# PCB.net
KiCad netlist of a schematic drawn in EasyEDA Pro
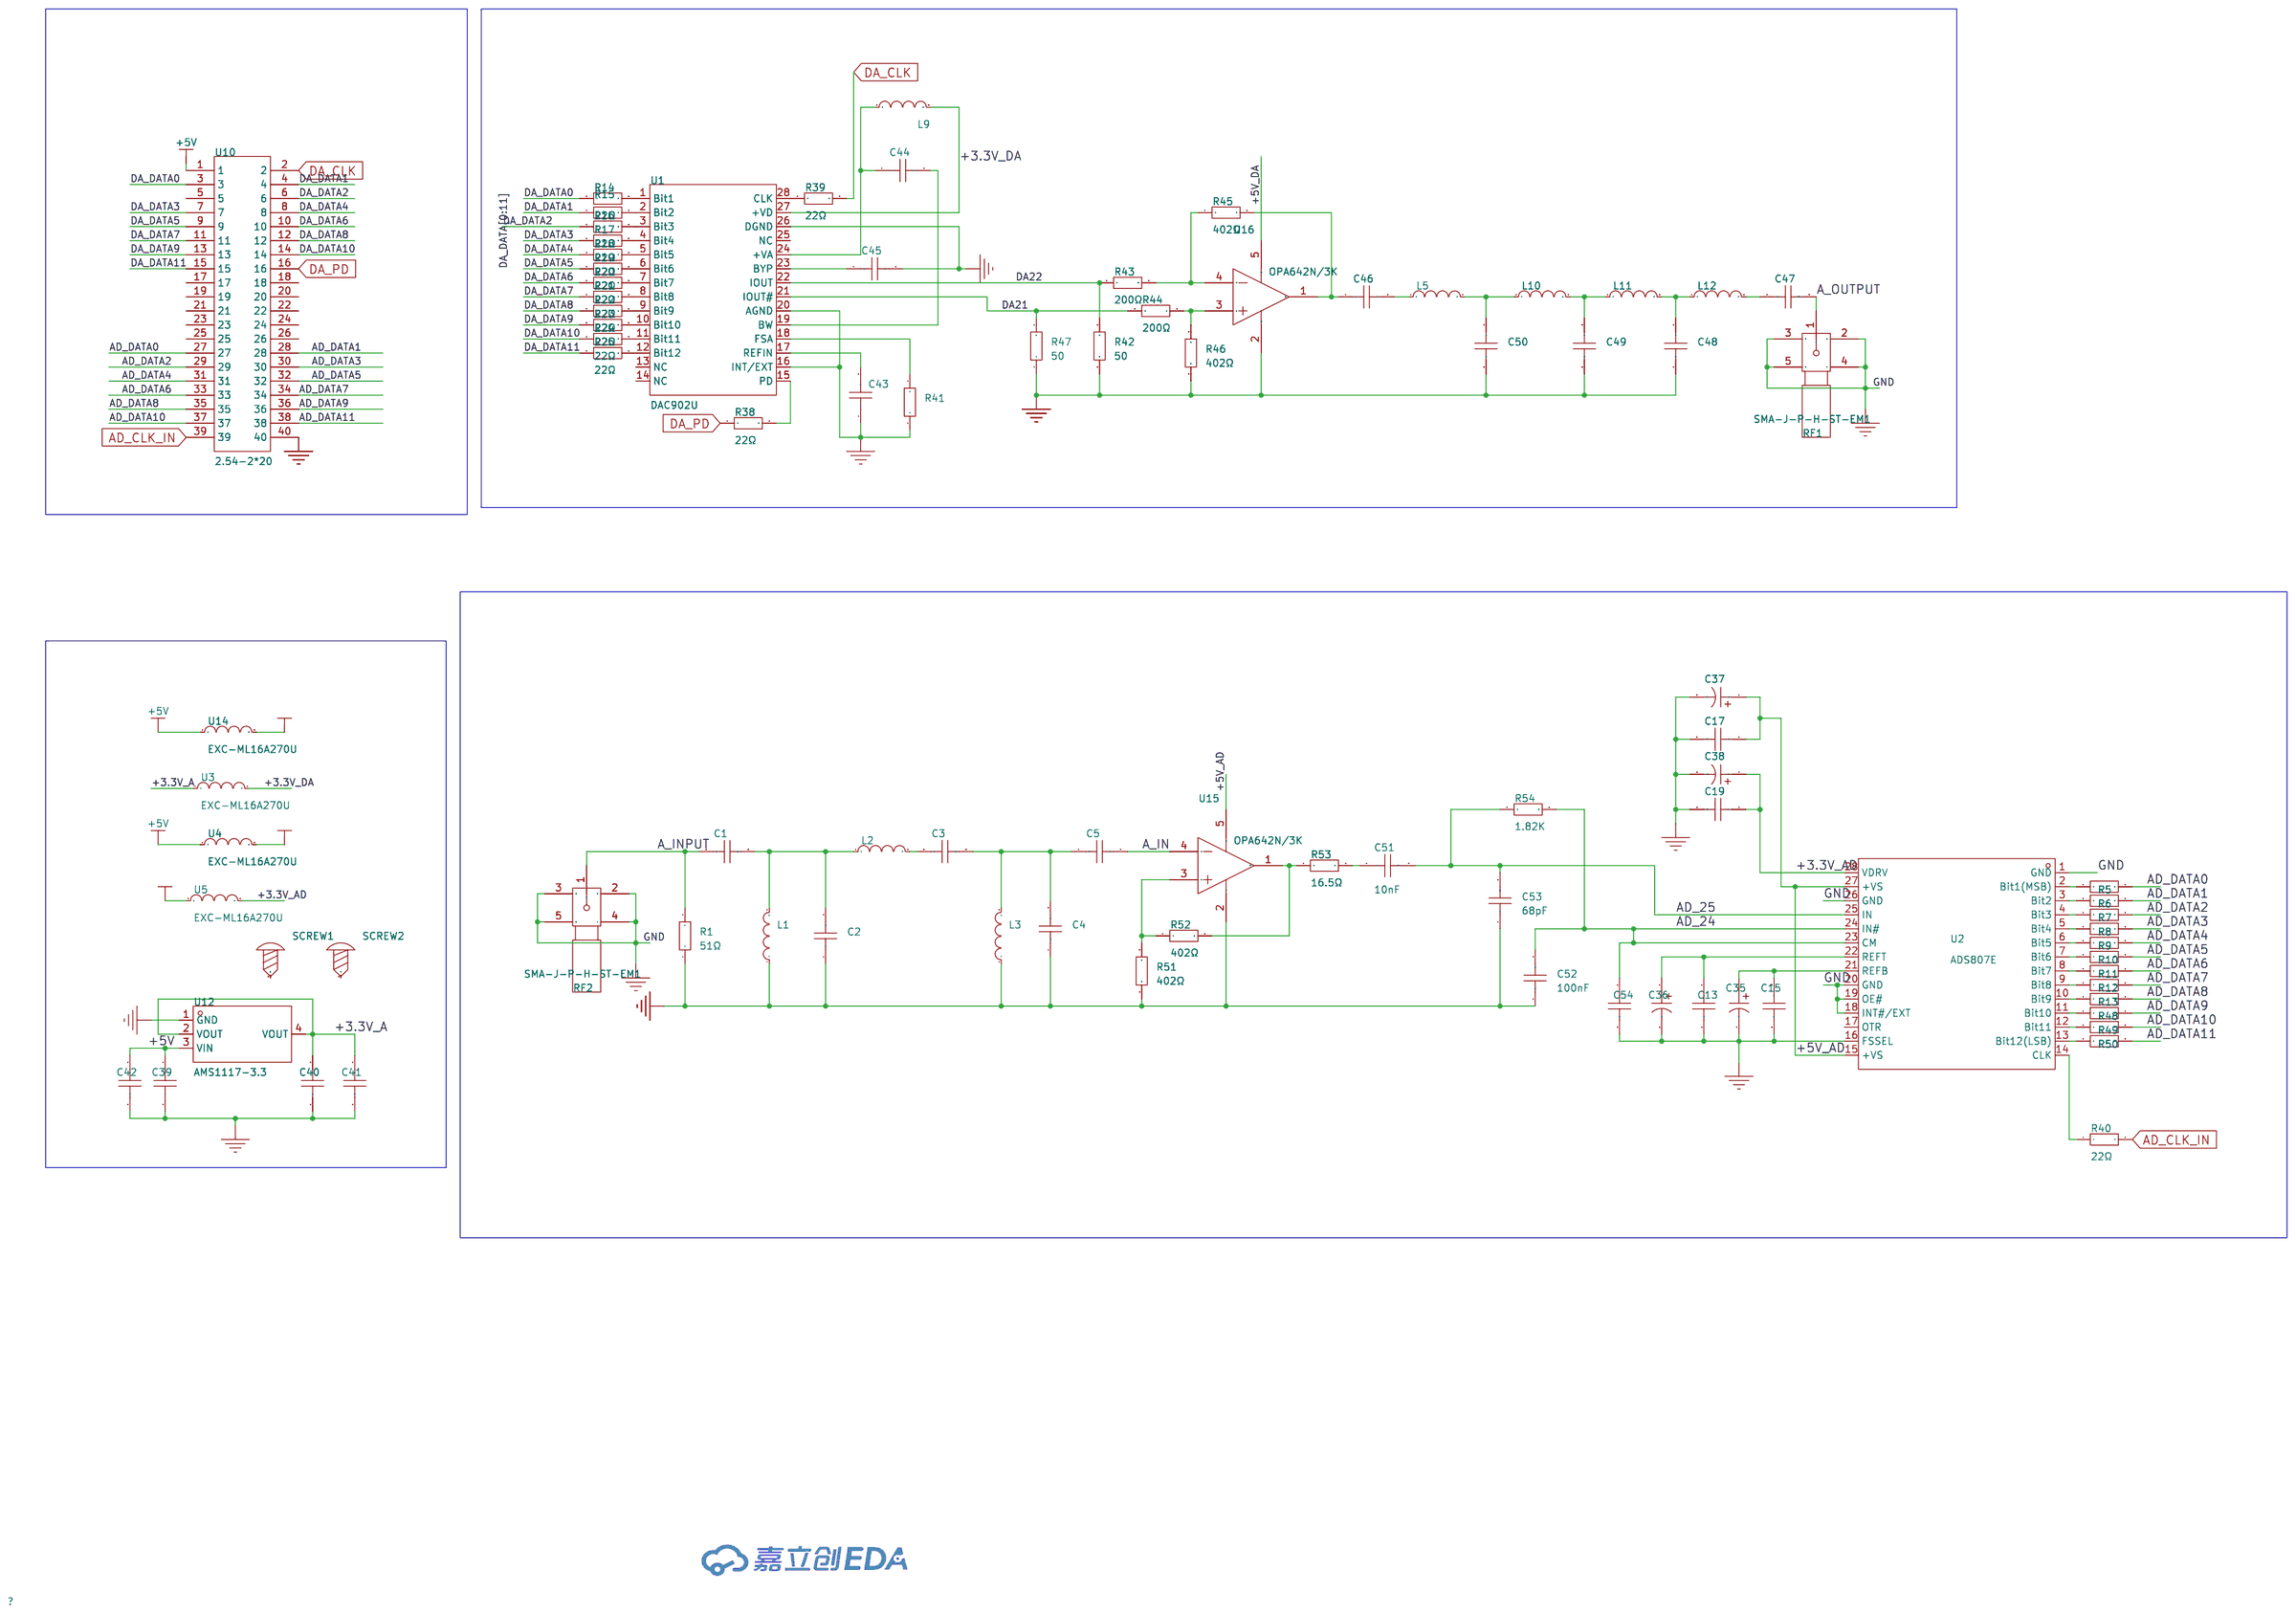
[diagram p0: schematic sheet]

(export (version "E")
  (design (tool "Eeschema 10.0.6"))
  (components
    (comp (ref "C1")
      (value "100nF")
      (footprint "easyedapro:D0805")
      (fields
        (field (name "Manufacturer Part") "CC0805KRX7R9BB104")
        (field (name "Manufacturer") "YAGEO(国巨)")
      )
      (libsource (lib "easyedapro") (part "CAP_0603"))
    )
    (comp (ref "C2")
      (value "100nF")
      (footprint "easyedapro:D0805")
      (fields
        (field (name "Manufacturer Part") "CC0805KRX7R9BB104")
        (field (name "Manufacturer") "YAGEO(国巨)")
      )
      (libsource (lib "easyedapro") (part "CAP_0603"))
    )
    (comp (ref "C3")
      (value "100nF")
      (footprint "easyedapro:D0805")
      (fields
        (field (name "Manufacturer Part") "CC0805KRX7R9BB104")
        (field (name "Manufacturer") "YAGEO(国巨)")
      )
      (libsource (lib "easyedapro") (part "CAP_0603"))
    )
    (comp (ref "C4")
      (value "100nF")
      (footprint "easyedapro:D0805")
      (fields
        (field (name "Manufacturer Part") "CC0805KRX7R9BB104")
        (field (name "Manufacturer") "YAGEO(国巨)")
      )
      (libsource (lib "easyedapro") (part "CAP_0603"))
    )
    (comp (ref "C5")
      (value "100nF")
      (footprint "easyedapro:D0805")
      (fields
        (field (name "Manufacturer Part") "CC0805KRX7R9BB104")
        (field (name "Manufacturer") "YAGEO(国巨)")
      )
      (libsource (lib "easyedapro") (part "CAP_0603"))
    )
    (comp (ref "C13")
      (value "100nF")
      (footprint "easyedapro:D0805")
      (fields
        (field (name "Manufacturer Part") "CC0805KRX7R9BB104")
        (field (name "Manufacturer") "YAGEO(国巨)")
      )
      (libsource (lib "easyedapro") (part "CAP_0603"))
    )
    (comp (ref "C15")
      (value "100nF")
      (footprint "easyedapro:D0805")
      (fields
        (field (name "Manufacturer Part") "CC0805KRX7R9BB104")
        (field (name "Manufacturer") "YAGEO(国巨)")
      )
      (libsource (lib "easyedapro") (part "CAP_0603"))
    )
    (comp (ref "C17")
      (value "100nF")
      (footprint "easyedapro:D0805")
      (fields
        (field (name "Manufacturer Part") "CC0805KRX7R9BB104")
        (field (name "Manufacturer") "YAGEO(国巨)")
      )
      (libsource (lib "easyedapro") (part "CAP_0603"))
    )
    (comp (ref "C19")
      (value "100nF")
      (footprint "easyedapro:D0805")
      (fields
        (field (name "Manufacturer Part") "CC0805KRX7R9BB104")
        (field (name "Manufacturer") "YAGEO(国巨)")
      )
      (libsource (lib "easyedapro") (part "CAP_0603"))
    )
    (comp (ref "C35")
      (value "10uF")
      (footprint "easyedapro:R1206-1")
      (fields
        (field (name "Manufacturer Part") "GVT1E227M0608CNVC")
        (field (name "Manufacturer") "HRK(鸿瑞凯电子)")
      )
      (libsource (lib "easyedapro") (part "GVT1E227M0608CNVC"))
    )
    (comp (ref "C36")
      (value "10uF")
      (footprint "easyedapro:R1206-1")
      (fields
        (field (name "Manufacturer Part") "GVT1E227M0608CNVC")
        (field (name "Manufacturer") "HRK(鸿瑞凯电子)")
      )
      (libsource (lib "easyedapro") (part "GVT1E227M0608CNVC"))
    )
    (comp (ref "C37")
      (value "10uF")
      (footprint "easyedapro:R1206-1")
      (fields
        (field (name "Manufacturer Part") "GVT1E227M0608CNVC")
        (field (name "Manufacturer") "HRK(鸿瑞凯电子)")
      )
      (libsource (lib "easyedapro") (part "GVT1E227M0608CNVC"))
    )
    (comp (ref "C38")
      (value "10uF")
      (footprint "easyedapro:R1206-1")
      (fields
        (field (name "Manufacturer Part") "GVT1E227M0608CNVC")
        (field (name "Manufacturer") "HRK(鸿瑞凯电子)")
      )
      (libsource (lib "easyedapro") (part "GVT1E227M0608CNVC"))
    )
    (comp (ref "C39")
      (value "100nF")
      (footprint "easyedapro:D0805")
      (fields (field (name "Manufacturer Part") "0805B104K500NT") (field (name "Manufacturer") "FH(风华)"))
      (libsource (lib "easyedapro") (part "CAP_0603"))
    )
    (comp (ref "C40")
      (value "100nF")
      (footprint "easyedapro:D0805")
      (fields (field (name "Manufacturer Part") "0805B104K500NT") (field (name "Manufacturer") "FH(风华)"))
      (libsource (lib "easyedapro") (part "CAP_0603"))
    )
    (comp (ref "C41")
      (value "22uF")
      (footprint "easyedapro:D0805")
      (fields
        (field (name "Manufacturer Part") "CL21A226MAQNNNE")
        (field (name "Manufacturer") "SAMSUNG(三星)")
      )
      (libsource (lib "easyedapro") (part "CAP_0603"))
    )
    (comp (ref "C42")
      (value "22uF")
      (footprint "easyedapro:D0805")
      (fields
        (field (name "Manufacturer Part") "CL21A226MAQNNNE")
        (field (name "Manufacturer") "SAMSUNG(三星)")
      )
      (libsource (lib "easyedapro") (part "CAP_0603"))
    )
    (comp (ref "C43")
      (value "100nF")
      (footprint "easyedapro:D0805")
      (fields
        (field (name "Manufacturer Part") "CC0805KRX7R9BB104")
        (field (name "Manufacturer") "YAGEO(国巨)")
      )
      (libsource (lib "easyedapro") (part "CAP_0603"))
    )
    (comp (ref "C44")
      (value "100nF")
      (footprint "easyedapro:D0805")
      (fields
        (field (name "Manufacturer Part") "CC0805KRX7R9BB104")
        (field (name "Manufacturer") "YAGEO(国巨)")
      )
      (libsource (lib "easyedapro") (part "CAP_0603"))
    )
    (comp (ref "C45")
      (value "100nF")
      (footprint "easyedapro:D0805")
      (fields
        (field (name "Manufacturer Part") "CC0805KRX7R9BB104")
        (field (name "Manufacturer") "YAGEO(国巨)")
      )
      (libsource (lib "easyedapro") (part "CAP_0603"))
    )
    (comp (ref "C46")
      (value "100nF")
      (footprint "easyedapro:D0805")
      (fields
        (field (name "Manufacturer Part") "CC0805KRX7R9BB104")
        (field (name "Manufacturer") "YAGEO(国巨)")
      )
      (libsource (lib "easyedapro") (part "CAP_0603"))
    )
    (comp (ref "C47")
      (value "100nF")
      (footprint "easyedapro:D0805")
      (fields
        (field (name "Manufacturer Part") "CC0805KRX7R9BB104")
        (field (name "Manufacturer") "YAGEO(国巨)")
      )
      (libsource (lib "easyedapro") (part "CAP_0603"))
    )
    (comp (ref "C48")
      (value "500pF")
      (footprint "easyedapro:D0805")
      (fields (field (name "Manufacturer Part") "0805CG501J500NT") (field (name "Manufacturer") "FH(风华)"))
      (libsource (lib "easyedapro") (part "CAP_0603"))
    )
    (comp (ref "C49")
      (value "850pF")
      (footprint "easyedapro:D0805")
      (fields
        (field (name "Manufacturer Part") "C06BL851X-5ZN-X0T")
        (field (name "Manufacturer") "Knowles(楼氏)")
      )
      (libsource (lib "easyedapro") (part "CAP_0603"))
    )
    (comp (ref "C50")
      (value "500pF")
      (footprint "easyedapro:D0805")
      (fields (field (name "Manufacturer Part") "0805CG501J500NT") (field (name "Manufacturer") "FH(风华)"))
      (libsource (lib "easyedapro") (part "CAP_0603"))
    )
    (comp (ref "C51")
      (value "10nF")
      (footprint "easyedapro:C0603")
      (fields
        (field (name "Manufacturer Part") "CC0805KRX7R9BB104")
        (field (name "Manufacturer") "YAGEO(国巨)")
      )
      (libsource (lib "easyedapro") (part "Capacitance"))
    )
    (comp (ref "C52")
      (value "100nF")
      (footprint "easyedapro:C0603")
      (fields
        (field (name "Manufacturer Part") "CC0805KRX7R9BB104")
        (field (name "Manufacturer") "YAGEO(国巨)")
      )
      (libsource (lib "easyedapro") (part "Capacitance"))
    )
    (comp (ref "C53")
      (value "68pF")
      (footprint "easyedapro:C0603")
      (fields (field (name "Manufacturer Part") "0805CG680J500NT") (field (name "Manufacturer") "FH(风华)"))
      (libsource (lib "easyedapro") (part "Capacitance"))
    )
    (comp (ref "C54")
      (value "100nF")
      (footprint "easyedapro:D0805")
      (fields
        (field (name "Manufacturer Part") "CC0805KRX7R9BB104")
        (field (name "Manufacturer") "YAGEO(国巨)")
      )
      (libsource (lib "easyedapro") (part "CAP_0603"))
    )
    (comp (ref "L1")
      (value "1uH")
      (footprint "easyedapro:D0805")
      (fields
        (field (name "Manufacturer Part") "SDFL2012Q1R0KTF")
        (field (name "Manufacturer") "Sunlord(顺络)")
      )
      (libsource (lib "easyedapro") (part "L_0603"))
    )
    (comp (ref "L2")
      (value "1uH")
      (footprint "easyedapro:D0805")
      (fields
        (field (name "Manufacturer Part") "SDFL2012Q1R0KTF")
        (field (name "Manufacturer") "Sunlord(顺络)")
      )
      (libsource (lib "easyedapro") (part "L_0603"))
    )
    (comp (ref "L3")
      (value "1uH")
      (footprint "easyedapro:D0805")
      (fields
        (field (name "Manufacturer Part") "SDFL2012Q1R0KTF")
        (field (name "Manufacturer") "Sunlord(顺络)")
      )
      (libsource (lib "easyedapro") (part "L_0603"))
    )
    (comp (ref "L5")
      (value "500nH")
      (footprint "easyedapro:D0805")
      (fields
        (field (name "Manufacturer Part") "CKP1608DR50M-T")
        (field (name "Manufacturer") "TAIYO YUDEN(太诱)")
      )
      (libsource (lib "easyedapro") (part "L_0603"))
    )
    (comp (ref "L9")
      (value "1uH")
      (footprint "easyedapro:D0805")
      (fields
        (field (name "Manufacturer Part") "SDFL2012Q1R0KTF")
        (field (name "Manufacturer") "Sunlord(顺络)")
      )
      (libsource (lib "easyedapro") (part "L_0603"))
    )
    (comp (ref "L10")
      (value "2uH")
      (footprint "easyedapro:D0805")
      (fields (field (name "Manufacturer Part") "LQW21FT2R0M0HL") (field (name "Manufacturer") "muRata(村田)"))
      (libsource (lib "easyedapro") (part "L_0603"))
    )
    (comp (ref "L11")
      (value "2uH")
      (footprint "easyedapro:D0805")
      (fields (field (name "Manufacturer Part") "LQW21FT2R0M0HL") (field (name "Manufacturer") "muRata(村田)"))
      (libsource (lib "easyedapro") (part "L_0603"))
    )
    (comp (ref "L12")
      (value "500nH")
      (footprint "easyedapro:D0805")
      (fields
        (field (name "Manufacturer Part") "CKP1608DR50M-T")
        (field (name "Manufacturer") "TAIYO YUDEN(太诱)")
      )
      (libsource (lib "easyedapro") (part "L_0603"))
    )
    (comp (ref "R1")
      (value "51Ω")
      (footprint "easyedapro:R0603")
      (fields
        (field (name "Manufacturer Part") "0805W8F510JT5E")
        (field (name "Manufacturer") "UNI-ROYAL(厚声)")
      )
      (libsource (lib "easyedapro") (part "电阻"))
    )
    (comp (ref "R5")
      (value "22Ω")
      (footprint "easyedapro:R0805")
      (fields
        (field (name "Manufacturer Part") "0805W8F2002T5E")
        (field (name "Manufacturer") "UNI-ROYAL(厚声)")
      )
      (libsource (lib "easyedapro") (part "0805W8F2002T5E"))
    )
    (comp (ref "R6")
      (value "22Ω")
      (footprint "easyedapro:R0805")
      (fields
        (field (name "Manufacturer Part") "0805W8F2002T5E")
        (field (name "Manufacturer") "UNI-ROYAL(厚声)")
      )
      (libsource (lib "easyedapro") (part "0805W8F2002T5E"))
    )
    (comp (ref "R7")
      (value "22Ω")
      (footprint "easyedapro:R0805")
      (fields
        (field (name "Manufacturer Part") "0805W8F2002T5E")
        (field (name "Manufacturer") "UNI-ROYAL(厚声)")
      )
      (libsource (lib "easyedapro") (part "0805W8F2002T5E"))
    )
    (comp (ref "R8")
      (value "22Ω")
      (footprint "easyedapro:R0805")
      (fields
        (field (name "Manufacturer Part") "0805W8F2002T5E")
        (field (name "Manufacturer") "UNI-ROYAL(厚声)")
      )
      (libsource (lib "easyedapro") (part "0805W8F2002T5E"))
    )
    (comp (ref "R9")
      (value "22Ω")
      (footprint "easyedapro:R0805")
      (fields
        (field (name "Manufacturer Part") "0805W8F2002T5E")
        (field (name "Manufacturer") "UNI-ROYAL(厚声)")
      )
      (libsource (lib "easyedapro") (part "0805W8F2002T5E"))
    )
    (comp (ref "R10")
      (value "22Ω")
      (footprint "easyedapro:R0805")
      (fields
        (field (name "Manufacturer Part") "0805W8F2002T5E")
        (field (name "Manufacturer") "UNI-ROYAL(厚声)")
      )
      (libsource (lib "easyedapro") (part "0805W8F2002T5E"))
    )
    (comp (ref "R11")
      (value "22Ω")
      (footprint "easyedapro:R0805")
      (fields
        (field (name "Manufacturer Part") "0805W8F2002T5E")
        (field (name "Manufacturer") "UNI-ROYAL(厚声)")
      )
      (libsource (lib "easyedapro") (part "0805W8F2002T5E"))
    )
    (comp (ref "R12")
      (value "22Ω")
      (footprint "easyedapro:R0805")
      (fields
        (field (name "Manufacturer Part") "0805W8F2002T5E")
        (field (name "Manufacturer") "UNI-ROYAL(厚声)")
      )
      (libsource (lib "easyedapro") (part "0805W8F2002T5E"))
    )
    (comp (ref "R13")
      (value "22Ω")
      (footprint "easyedapro:R0805")
      (fields
        (field (name "Manufacturer Part") "0805W8F2002T5E")
        (field (name "Manufacturer") "UNI-ROYAL(厚声)")
      )
      (libsource (lib "easyedapro") (part "0805W8F2002T5E"))
    )
    (comp (ref "R14")
      (value "22Ω")
      (footprint "easyedapro:R0603")
      (fields
        (field (name "Manufacturer Part") "0805W8F220JT5E")
        (field (name "Manufacturer") "UNI-ROYAL(厚声)")
      )
      (libsource (lib "easyedapro") (part "电阻"))
    )
    (comp (ref "R15")
      (value "22Ω")
      (footprint "easyedapro:R0603")
      (fields
        (field (name "Manufacturer Part") "0805W8F220JT5E")
        (field (name "Manufacturer") "UNI-ROYAL(厚声)")
      )
      (libsource (lib "easyedapro") (part "电阻"))
    )
    (comp (ref "R16")
      (value "22Ω")
      (footprint "easyedapro:R0603")
      (fields
        (field (name "Manufacturer Part") "0805W8F220JT5E")
        (field (name "Manufacturer") "UNI-ROYAL(厚声)")
      )
      (libsource (lib "easyedapro") (part "电阻"))
    )
    (comp (ref "R17")
      (value "22Ω")
      (footprint "easyedapro:R0603")
      (fields
        (field (name "Manufacturer Part") "0805W8F220JT5E")
        (field (name "Manufacturer") "UNI-ROYAL(厚声)")
      )
      (libsource (lib "easyedapro") (part "电阻"))
    )
    (comp (ref "R18")
      (value "22Ω")
      (footprint "easyedapro:R0603")
      (fields
        (field (name "Manufacturer Part") "0805W8F220JT5E")
        (field (name "Manufacturer") "UNI-ROYAL(厚声)")
      )
      (libsource (lib "easyedapro") (part "电阻"))
    )
    (comp (ref "R19")
      (value "22Ω")
      (footprint "easyedapro:R0603")
      (fields
        (field (name "Manufacturer Part") "0805W8F220JT5E")
        (field (name "Manufacturer") "UNI-ROYAL(厚声)")
      )
      (libsource (lib "easyedapro") (part "电阻"))
    )
    (comp (ref "R20")
      (value "22Ω")
      (footprint "easyedapro:R0603")
      (fields
        (field (name "Manufacturer Part") "0805W8F220JT5E")
        (field (name "Manufacturer") "UNI-ROYAL(厚声)")
      )
      (libsource (lib "easyedapro") (part "电阻"))
    )
    (comp (ref "R21")
      (value "22Ω")
      (footprint "easyedapro:R0603")
      (fields
        (field (name "Manufacturer Part") "0805W8F220JT5E")
        (field (name "Manufacturer") "UNI-ROYAL(厚声)")
      )
      (libsource (lib "easyedapro") (part "电阻"))
    )
    (comp (ref "R22")
      (value "22Ω")
      (footprint "easyedapro:R0603")
      (fields
        (field (name "Manufacturer Part") "0805W8F220JT5E")
        (field (name "Manufacturer") "UNI-ROYAL(厚声)")
      )
      (libsource (lib "easyedapro") (part "电阻"))
    )
    (comp (ref "R23")
      (value "22Ω")
      (footprint "easyedapro:R0603")
      (fields
        (field (name "Manufacturer Part") "0805W8F220JT5E")
        (field (name "Manufacturer") "UNI-ROYAL(厚声)")
      )
      (libsource (lib "easyedapro") (part "电阻"))
    )
    (comp (ref "R24")
      (value "22Ω")
      (footprint "easyedapro:R0603")
      (fields
        (field (name "Manufacturer Part") "0805W8F220JT5E")
        (field (name "Manufacturer") "UNI-ROYAL(厚声)")
      )
      (libsource (lib "easyedapro") (part "电阻"))
    )
    (comp (ref "R25")
      (value "22Ω")
      (footprint "easyedapro:R0603")
      (fields
        (field (name "Manufacturer Part") "0805W8F220JT5E")
        (field (name "Manufacturer") "UNI-ROYAL(厚声)")
      )
      (libsource (lib "easyedapro") (part "电阻"))
    )
    (comp (ref "R38")
      (value "22Ω")
      (footprint "easyedapro:R0603")
      (fields
        (field (name "Manufacturer Part") "0805W8F220JT5E")
        (field (name "Manufacturer") "UNI-ROYAL(厚声)")
      )
      (libsource (lib "easyedapro") (part "电阻"))
    )
    (comp (ref "R39")
      (value "22Ω")
      (footprint "easyedapro:R0603")
      (fields
        (field (name "Manufacturer Part") "0805W8F220JT5E")
        (field (name "Manufacturer") "UNI-ROYAL(厚声)")
      )
      (libsource (lib "easyedapro") (part "电阻"))
    )
    (comp (ref "R40")
      (value "22Ω")
      (footprint "easyedapro:R0603")
      (fields
        (field (name "Manufacturer Part") "0805W8F220JT5E")
        (field (name "Manufacturer") "UNI-ROYAL(厚声)")
      )
      (libsource (lib "easyedapro") (part "电阻"))
    )
    (comp (ref "R41")
      (value "2kΩ")
      (footprint "easyedapro:D0805")
      (fields
        (field (name "Manufacturer Part") "0805W8F2001T5E")
        (field (name "Manufacturer") "UNI-ROYAL(厚声)")
      )
      (libsource (lib "easyedapro") (part "Res_0603"))
    )
    (comp (ref "R42")
      (value "50")
      (footprint "easyedapro:R0603")
      (fields (field (name "Manufacturer Part") "ERJ6ENF28R7V") (field (name "Manufacturer") "PANASONIC(松下)"))
      (libsource (lib "easyedapro") (part "电阻"))
    )
    (comp (ref "R43")
      (value "200Ω")
      (footprint "easyedapro:R0603")
      (fields
        (field (name "Manufacturer Part") "0805W8F2000T5E")
        (field (name "Manufacturer") "UNI-ROYAL(厚声)")
      )
      (libsource (lib "easyedapro") (part "电阻"))
    )
    (comp (ref "R44")
      (value "200Ω")
      (footprint "easyedapro:R0603")
      (fields
        (field (name "Manufacturer Part") "0805W8F2000T5E")
        (field (name "Manufacturer") "UNI-ROYAL(厚声)")
      )
      (libsource (lib "easyedapro") (part "电阻"))
    )
    (comp (ref "R45")
      (value "402Ω")
      (footprint "easyedapro:R0603")
      (fields (field (name "Manufacturer Part") "FRC0805F4020TS") (field (name "Manufacturer") "FOJAN(富捷)"))
      (libsource (lib "easyedapro") (part "电阻"))
    )
    (comp (ref "R46")
      (value "402Ω")
      (footprint "easyedapro:R0603")
      (fields (field (name "Manufacturer Part") "FRC0805F4020TS") (field (name "Manufacturer") "FOJAN(富捷)"))
      (libsource (lib "easyedapro") (part "电阻"))
    )
    (comp (ref "R47")
      (value "50")
      (footprint "easyedapro:R0603")
      (fields (field (name "Manufacturer Part") "ERJ6ENF26R1V") (field (name "Manufacturer") "PANASONIC(松下)"))
      (libsource (lib "easyedapro") (part "电阻"))
    )
    (comp (ref "R48")
      (value "22Ω")
      (footprint "easyedapro:R0805")
      (fields
        (field (name "Manufacturer Part") "0805W8F2002T5E")
        (field (name "Manufacturer") "UNI-ROYAL(厚声)")
      )
      (libsource (lib "easyedapro") (part "0805W8F2002T5E"))
    )
    (comp (ref "R49")
      (value "22Ω")
      (footprint "easyedapro:R0805")
      (fields
        (field (name "Manufacturer Part") "0805W8F2002T5E")
        (field (name "Manufacturer") "UNI-ROYAL(厚声)")
      )
      (libsource (lib "easyedapro") (part "0805W8F2002T5E"))
    )
    (comp (ref "R50")
      (value "22Ω")
      (footprint "easyedapro:R0805")
      (fields
        (field (name "Manufacturer Part") "0805W8F2002T5E")
        (field (name "Manufacturer") "UNI-ROYAL(厚声)")
      )
      (libsource (lib "easyedapro") (part "0805W8F2002T5E"))
    )
    (comp (ref "R51")
      (value "402Ω")
      (footprint "easyedapro:R0603")
      (fields (field (name "Manufacturer Part") "FRC0805F4020TS") (field (name "Manufacturer") "FOJAN(富捷)"))
      (libsource (lib "easyedapro") (part "电阻"))
    )
    (comp (ref "R52")
      (value "402Ω")
      (footprint "easyedapro:R0603")
      (fields (field (name "Manufacturer Part") "FRC0805F4020TS") (field (name "Manufacturer") "FOJAN(富捷)"))
      (libsource (lib "easyedapro") (part "电阻"))
    )
    (comp (ref "R53")
      (value "16.5Ω")
      (footprint "easyedapro:R0603")
      (fields (field (name "Manufacturer Part") "RC0805FR-0716R5L") (field (name "Manufacturer") "YAGEO(国巨)"))
      (libsource (lib "easyedapro") (part "电阻"))
    )
    (comp (ref "R54")
      (value "1.82K")
      (footprint "easyedapro:R0603")
      (libsource (lib "easyedapro") (part "电阻"))
    )
    (comp (ref "RF1")
      (value "SMA-J-P-H-ST-EM1")
      (footprint "easyedapro:SMA-SMD_SMA-J-P-H-ST-EM1")
      (fields (field (name "Manufacturer") "SAMTEC"))
      (libsource (lib "easyedapro") (part "SMA-J-P-H-ST-EM1"))
    )
    (comp (ref "RF2")
      (value "SMA-J-P-H-ST-EM1")
      (footprint "easyedapro:SMA-SMD_SMA-J-P-H-ST-EM1")
      (fields (field (name "Manufacturer") "SAMTEC"))
      (libsource (lib "easyedapro") (part "SMA-J-P-H-ST-EM1"))
    )
    (comp (ref "SCREW1")
      (value "~")
      (footprint "easyedapro:M3螺丝")
      (libsource (lib "easyedapro") (part "螺丝孔"))
    )
    (comp (ref "SCREW2")
      (value "~")
      (footprint "easyedapro:M3螺丝")
      (libsource (lib "easyedapro") (part "螺丝孔"))
    )
    (comp (ref "U1")
      (value "DAC902U")
      (footprint "easyedapro:SOIC-28_L18.0-W7.5-P1.27-LS10.3-BL")
      (description "分辨率:12位;接口类型:-;工作电压:2.7V~5.5V;稳定时间:30ns;积分非线性:1LSB;")
      (fields (field (name "Manufacturer") "TI(德州仪器)"))
      (libsource (lib "easyedapro") (part "DAC902U"))
    )
    (comp (ref "U2")
      (value "ADS807E")
      (footprint "easyedapro:SSOP-28_L10.2-W5.3-P0.65-LS7.8-BL")
      (fields (field (name "Manufacturer") "TI(德州仪器)"))
      (libsource (lib "easyedapro") (part "ADS807E"))
    )
    (comp (ref "U3")
      (value "EXC-ML16A270U")
      (footprint "easyedapro:L0603")
      (fields (field (name "Manufacturer") "PANASONIC(松下)"))
      (libsource (lib "easyedapro") (part "EXC-ML16A270U"))
    )
    (comp (ref "U4")
      (value "EXC-ML16A270U")
      (footprint "easyedapro:L0603")
      (fields (field (name "Manufacturer") "PANASONIC(松下)"))
      (libsource (lib "easyedapro") (part "EXC-ML16A270U"))
    )
    (comp (ref "U5")
      (value "EXC-ML16A270U")
      (footprint "easyedapro:L0603")
      (fields (field (name "Manufacturer") "PANASONIC(松下)"))
      (libsource (lib "easyedapro") (part "EXC-ML16A270U"))
    )
    (comp (ref "U10")
      (value "2.54-2*20")
      (footprint "easyedapro:HDR-TH_40P-P2.54-V-F-R2-C20-S2.54")
      (fields (field (name "Manufacturer") "ZHOURI(洲日)"))
      (libsource (lib "easyedapro") (part "2.54-2*20"))
    )
    (comp (ref "U12")
      (value "AMS1117-3.3")
      (footprint "easyedapro:SOT-223-3_L6.5-W3.4-P2.30-LS7.0-BR")
      (fields (field (name "Manufacturer") "AMS"))
      (libsource (lib "easyedapro") (part "AMS1117-3.3_C6186"))
    )
    (comp (ref "U14")
      (value "EXC-ML16A270U")
      (footprint "easyedapro:L0603")
      (fields (field (name "Manufacturer") "PANASONIC(松下)"))
      (libsource (lib "easyedapro") (part "EXC-ML16A270U"))
    )
    (comp (ref "U15")
      (value "OPA642N/3K")
      (footprint "easyedapro:SOT-23-5_L2.9-W1.6-P0.95-LS2.8-BR")
      (description "放大器数:单路;增益带宽积(GBP):210MHz;输入偏置电流(Ib):25uA;压摆率(SR):380V/us;带宽(-3db):-;")
      (fields (field (name "Manufacturer") "TI(德州仪器)"))
      (libsource (lib "easyedapro") (part "OPA642N/3K"))
    )
    (comp (ref "U16")
      (value "OPA642N/3K")
      (footprint "easyedapro:SOT-23-5_L2.9-W1.6-P0.95-LS2.8-BR")
      (description "放大器数:单路;增益带宽积(GBP):210MHz;输入偏置电流(Ib):25uA;压摆率(SR):380V/us;带宽(-3db):-;")
      (fields (field (name "Manufacturer") "TI(德州仪器)"))
      (libsource (lib "easyedapro") (part "OPA642N/3K"))
    )
  )
  (nets
    (net (code "1") (name "+3.3V_A") (class "Default")
      (node (ref "C40") (pin "1") (pinfunction "1_1") (pintype "unspecified"))
      (node (ref "C41") (pin "1") (pinfunction "1_1") (pintype "unspecified"))
      (node (ref "U12") (pin "2") (pinfunction "VOUT_2") (pintype "unspecified"))
      (node (ref "U12") (pin "4") (pinfunction "VOUT_4") (pintype "unspecified"))
      (node (ref "U3") (pin "1") (pinfunction "1_1") (pintype "unspecified"))
      (node (ref "U5") (pin "1") (pinfunction "1_1") (pintype "unspecified"))
    )
    (net (code "2") (name "+5V") (class "Default")
      (node (ref "C39") (pin "1") (pinfunction "1_1") (pintype "unspecified"))
      (node (ref "C42") (pin "1") (pinfunction "1_1") (pintype "unspecified"))
      (node (ref "U10") (pin "1") (pinfunction "1_1") (pintype "unspecified"))
      (node (ref "U12") (pin "3") (pinfunction "VIN_3") (pintype "unspecified"))
      (node (ref "U14") (pin "1") (pinfunction "1_1") (pintype "unspecified"))
      (node (ref "U4") (pin "1") (pinfunction "1_1") (pintype "unspecified"))
    )
    (net (code "3") (name "+5V_AD") (class "Default")
      (node (ref "C17") (pin "1") (pinfunction "1_1") (pintype "unspecified"))
      (node (ref "C37") (pin "1") (pinfunction "1_1") (pintype "unspecified"))
      (node (ref "U15") (pin "5") (pinfunction "VS+_5") (pintype "unspecified"))
      (node (ref "U2") (pin "15") (pinfunction "+VS_15") (pintype "unspecified"))
      (node (ref "U2") (pin "27") (pinfunction "+VS_27") (pintype "unspecified"))
      (node (ref "U4") (pin "2") (pinfunction "2_2") (pintype "unspecified"))
    )
    (net (code "4") (name "+5V_DA") (class "Default")
      (node (ref "U14") (pin "2") (pinfunction "2_2") (pintype "unspecified"))
      (node (ref "U16") (pin "5") (pinfunction "VS+_5") (pintype "unspecified"))
    )
    (net (code "5") (name "/+3.3V_AD") (class "Default")
      (node (ref "C19") (pin "1") (pinfunction "1_1") (pintype "unspecified"))
      (node (ref "C38") (pin "1") (pinfunction "1_1") (pintype "unspecified"))
      (node (ref "U2") (pin "28") (pinfunction "VDRV_28") (pintype "unspecified"))
      (node (ref "U5") (pin "2") (pinfunction "2_2") (pintype "unspecified"))
    )
    (net (code "6") (name "/+3.3V_DA") (class "Default")
      (node (ref "L9") (pin "2") (pinfunction "2_2") (pintype "unspecified"))
      (node (ref "U1") (pin "27") (pinfunction "+VD_27") (pintype "unspecified"))
      (node (ref "U3") (pin "2") (pinfunction "2_2") (pintype "unspecified"))
    )
    (net (code "7") (name "/AD_24") (class "Default")
      (node (ref "C52") (pin "2") (pinfunction "2_2") (pintype "input"))
      (node (ref "C54") (pin "1") (pinfunction "1_1") (pintype "unspecified"))
      (node (ref "R54") (pin "2") (pinfunction "2_2") (pintype "input"))
      (node (ref "U2") (pin "23") (pinfunction "CM_23") (pintype "unspecified"))
      (node (ref "U2") (pin "24") (pinfunction "IN#_24") (pintype "unspecified"))
    )
    (net (code "8") (name "/AD_25") (class "Default")
      (node (ref "C51") (pin "2") (pinfunction "2_2") (pintype "input"))
      (node (ref "C53") (pin "2") (pinfunction "2_2") (pintype "input"))
      (node (ref "R54") (pin "1") (pinfunction "1_1") (pintype "input"))
      (node (ref "U2") (pin "25") (pinfunction "IN_25") (pintype "unspecified"))
    )
    (net (code "9") (name "/AD_DATA0") (class "Default")
      (node (ref "R5") (pin "2") (pinfunction "2_2") (pintype "unspecified"))
      (node (ref "U10") (pin "27") (pinfunction "27_27") (pintype "unspecified"))
    )
    (net (code "10") (name "/AD_DATA1") (class "Default")
      (node (ref "R6") (pin "2") (pinfunction "2_2") (pintype "unspecified"))
      (node (ref "U10") (pin "28") (pinfunction "28_28") (pintype "unspecified"))
    )
    (net (code "11") (name "/AD_DATA2") (class "Default")
      (node (ref "R7") (pin "2") (pinfunction "2_2") (pintype "unspecified"))
      (node (ref "U10") (pin "29") (pinfunction "29_29") (pintype "unspecified"))
    )
    (net (code "12") (name "/AD_DATA3") (class "Default")
      (node (ref "R8") (pin "2") (pinfunction "2_2") (pintype "unspecified"))
      (node (ref "U10") (pin "30") (pinfunction "30_30") (pintype "unspecified"))
    )
    (net (code "13") (name "/AD_DATA4") (class "Default")
      (node (ref "R9") (pin "2") (pinfunction "2_2") (pintype "unspecified"))
      (node (ref "U10") (pin "31") (pinfunction "31_31") (pintype "unspecified"))
    )
    (net (code "14") (name "/AD_DATA5") (class "Default")
      (node (ref "R10") (pin "2") (pinfunction "2_2") (pintype "unspecified"))
      (node (ref "U10") (pin "32") (pinfunction "32_32") (pintype "unspecified"))
    )
    (net (code "15") (name "/AD_DATA6") (class "Default")
      (node (ref "R11") (pin "2") (pinfunction "2_2") (pintype "unspecified"))
      (node (ref "U10") (pin "33") (pinfunction "33_33") (pintype "unspecified"))
    )
    (net (code "16") (name "/AD_DATA7") (class "Default")
      (node (ref "R12") (pin "2") (pinfunction "2_2") (pintype "unspecified"))
      (node (ref "U10") (pin "34") (pinfunction "34_34") (pintype "unspecified"))
    )
    (net (code "17") (name "/AD_DATA8") (class "Default")
      (node (ref "R13") (pin "2") (pinfunction "2_2") (pintype "unspecified"))
      (node (ref "U10") (pin "35") (pinfunction "35_35") (pintype "unspecified"))
    )
    (net (code "18") (name "/AD_DATA9") (class "Default")
      (node (ref "R48") (pin "2") (pinfunction "2_2") (pintype "unspecified"))
      (node (ref "U10") (pin "36") (pinfunction "36_36") (pintype "unspecified"))
    )
    (net (code "19") (name "/AD_DATA10") (class "Default")
      (node (ref "R49") (pin "2") (pinfunction "2_2") (pintype "unspecified"))
      (node (ref "U10") (pin "37") (pinfunction "37_37") (pintype "unspecified"))
    )
    (net (code "20") (name "/AD_DATA11") (class "Default")
      (node (ref "R50") (pin "2") (pinfunction "2_2") (pintype "unspecified"))
      (node (ref "U10") (pin "38") (pinfunction "38_38") (pintype "unspecified"))
    )
    (net (code "21") (name "/A_IN") (class "Default")
      (node (ref "C5") (pin "2") (pinfunction "2_2") (pintype "unspecified"))
      (node (ref "U15") (pin "4") (pinfunction "-IN_4") (pintype "unspecified"))
    )
    (net (code "22") (name "/A_INPUT") (class "Default")
      (node (ref "C1") (pin "1") (pinfunction "1_1") (pintype "unspecified"))
      (node (ref "R1") (pin "2") (pinfunction "2_2") (pintype "input"))
      (node (ref "RF2") (pin "1") (pinfunction "1_1") (pintype "unspecified"))
    )
    (net (code "23") (name "/A_OUTPUT") (class "Default")
      (node (ref "C47") (pin "2") (pinfunction "2_2") (pintype "unspecified"))
      (node (ref "RF1") (pin "1") (pinfunction "1_1") (pintype "unspecified"))
    )
    (net (code "24") (name "/DA21") (class "Default")
      (node (ref "R44") (pin "1") (pinfunction "1_1") (pintype "input"))
      (node (ref "R47") (pin "2") (pinfunction "2_2") (pintype "input"))
      (node (ref "U1") (pin "21") (pinfunction "IOUT#_21") (pintype "unspecified"))
    )
    (net (code "25") (name "/DA22") (class "Default")
      (node (ref "R42") (pin "2") (pinfunction "2_2") (pintype "input"))
      (node (ref "R43") (pin "1") (pinfunction "1_1") (pintype "input"))
      (node (ref "U1") (pin "22") (pinfunction "IOUT_22") (pintype "unspecified"))
    )
    (net (code "26") (name "/DA_DATA0") (class "Default")
      (node (ref "R14") (pin "1") (pinfunction "1_1") (pintype "input"))
      (node (ref "U10") (pin "3") (pinfunction "3_3") (pintype "unspecified"))
    )
    (net (code "27") (name "/DA_DATA1") (class "Default")
      (node (ref "R15") (pin "1") (pinfunction "1_1") (pintype "input"))
      (node (ref "U10") (pin "4") (pinfunction "4_4") (pintype "unspecified"))
    )
    (net (code "28") (name "/DA_DATA2") (class "Default")
      (node (ref "R16") (pin "1") (pinfunction "1_1") (pintype "input"))
      (node (ref "U10") (pin "6") (pinfunction "6_6") (pintype "unspecified"))
    )
    (net (code "29") (name "/DA_DATA3") (class "Default")
      (node (ref "R17") (pin "1") (pinfunction "1_1") (pintype "input"))
      (node (ref "U10") (pin "7") (pinfunction "7_7") (pintype "unspecified"))
    )
    (net (code "30") (name "/DA_DATA4") (class "Default")
      (node (ref "R18") (pin "1") (pinfunction "1_1") (pintype "input"))
      (node (ref "U10") (pin "8") (pinfunction "8_8") (pintype "unspecified"))
    )
    (net (code "31") (name "/DA_DATA5") (class "Default")
      (node (ref "R19") (pin "1") (pinfunction "1_1") (pintype "input"))
      (node (ref "U10") (pin "9") (pinfunction "9_9") (pintype "unspecified"))
    )
    (net (code "32") (name "/DA_DATA6") (class "Default")
      (node (ref "R20") (pin "1") (pinfunction "1_1") (pintype "input"))
      (node (ref "U10") (pin "10") (pinfunction "10_10") (pintype "unspecified"))
    )
    (net (code "33") (name "/DA_DATA7") (class "Default")
      (node (ref "R21") (pin "1") (pinfunction "1_1") (pintype "input"))
      (node (ref "U10") (pin "11") (pinfunction "11_11") (pintype "unspecified"))
    )
    (net (code "34") (name "/DA_DATA8") (class "Default")
      (node (ref "R22") (pin "1") (pinfunction "1_1") (pintype "input"))
      (node (ref "U10") (pin "12") (pinfunction "12_12") (pintype "unspecified"))
    )
    (net (code "35") (name "/DA_DATA9") (class "Default")
      (node (ref "R23") (pin "1") (pinfunction "1_1") (pintype "input"))
      (node (ref "U10") (pin "13") (pinfunction "13_13") (pintype "unspecified"))
    )
    (net (code "36") (name "/DA_DATA10") (class "Default")
      (node (ref "R24") (pin "1") (pinfunction "1_1") (pintype "input"))
      (node (ref "U10") (pin "14") (pinfunction "14_14") (pintype "unspecified"))
    )
    (net (code "37") (name "/DA_DATA11") (class "Default")
      (node (ref "R25") (pin "1") (pinfunction "1_1") (pintype "input"))
      (node (ref "U10") (pin "15") (pinfunction "15_15") (pintype "unspecified"))
    )
    (net (code "39") (name "AD_CLK_IN") (class "Default")
      (node (ref "R40") (pin "2") (pinfunction "2_2") (pintype "input"))
      (node (ref "U10") (pin "39") (pinfunction "39_39") (pintype "unspecified"))
    )
    (net (code "40") (name "DA_CLK") (class "Default")
      (node (ref "R39") (pin "2") (pinfunction "2_2") (pintype "input"))
      (node (ref "U10") (pin "2") (pinfunction "2_2") (pintype "unspecified"))
    )
    (net (code "41") (name "DA_PD") (class "Default")
      (node (ref "R38") (pin "1") (pinfunction "1_1") (pintype "input"))
      (node (ref "U10") (pin "16") (pinfunction "16_16") (pintype "unspecified"))
    )
    (net (code "42") (name "GND") (class "Default")
      (node (ref "C13") (pin "2") (pinfunction "2_2") (pintype "unspecified"))
      (node (ref "C15") (pin "2") (pinfunction "2_2") (pintype "unspecified"))
      (node (ref "C17") (pin "2") (pinfunction "2_2") (pintype "unspecified"))
      (node (ref "C19") (pin "2") (pinfunction "2_2") (pintype "unspecified"))
      (node (ref "C2") (pin "1") (pinfunction "1_1") (pintype "unspecified"))
      (node (ref "C35") (pin "2") (pinfunction "2_2") (pintype "unspecified"))
      (node (ref "C36") (pin "2") (pinfunction "2_2") (pintype "unspecified"))
      (node (ref "C37") (pin "2") (pinfunction "2_2") (pintype "unspecified"))
      (node (ref "C38") (pin "2") (pinfunction "2_2") (pintype "unspecified"))
      (node (ref "C39") (pin "2") (pinfunction "2_2") (pintype "unspecified"))
      (node (ref "C4") (pin "1") (pinfunction "1_1") (pintype "unspecified"))
      (node (ref "C40") (pin "2") (pinfunction "2_2") (pintype "unspecified"))
      (node (ref "C41") (pin "2") (pinfunction "2_2") (pintype "unspecified"))
      (node (ref "C42") (pin "2") (pinfunction "2_2") (pintype "unspecified"))
      (node (ref "C43") (pin "1") (pinfunction "1_1") (pintype "unspecified"))
      (node (ref "C45") (pin "2") (pinfunction "2_2") (pintype "unspecified"))
      (node (ref "C48") (pin "1") (pinfunction "1_1") (pintype "unspecified"))
      (node (ref "C49") (pin "1") (pinfunction "1_1") (pintype "unspecified"))
      (node (ref "C50") (pin "1") (pinfunction "1_1") (pintype "unspecified"))
      (node (ref "C52") (pin "1") (pinfunction "1_1") (pintype "input"))
      (node (ref "C53") (pin "1") (pinfunction "1_1") (pintype "input"))
      (node (ref "C54") (pin "2") (pinfunction "2_2") (pintype "unspecified"))
      (node (ref "L1") (pin "1") (pinfunction "1_1") (pintype "unspecified"))
      (node (ref "L3") (pin "1") (pinfunction "1_1") (pintype "unspecified"))
      (node (ref "R1") (pin "1") (pinfunction "1_1") (pintype "input"))
      (node (ref "R41") (pin "1") (pinfunction "1_1") (pintype "unspecified"))
      (node (ref "R42") (pin "1") (pinfunction "1_1") (pintype "input"))
      (node (ref "R46") (pin "1") (pinfunction "1_1") (pintype "input"))
      (node (ref "R47") (pin "1") (pinfunction "1_1") (pintype "input"))
      (node (ref "R51") (pin "1") (pinfunction "1_1") (pintype "input"))
      (node (ref "RF1") (pin "2") (pinfunction "2_2") (pintype "unspecified"))
      (node (ref "RF1") (pin "3") (pinfunction "3_3") (pintype "unspecified"))
      (node (ref "RF1") (pin "4") (pinfunction "4_4") (pintype "unspecified"))
      (node (ref "RF1") (pin "5") (pinfunction "5_5") (pintype "unspecified"))
      (node (ref "RF2") (pin "2") (pinfunction "2_2") (pintype "unspecified"))
      (node (ref "RF2") (pin "3") (pinfunction "3_3") (pintype "unspecified"))
      (node (ref "RF2") (pin "4") (pinfunction "4_4") (pintype "unspecified"))
      (node (ref "RF2") (pin "5") (pinfunction "5_5") (pintype "unspecified"))
      (node (ref "U1") (pin "16") (pinfunction "INT/EXT_16") (pintype "unspecified"))
      (node (ref "U1") (pin "20") (pinfunction "AGND_20") (pintype "unspecified"))
      (node (ref "U1") (pin "26") (pinfunction "DGND_26") (pintype "unspecified"))
      (node (ref "U10") (pin "40") (pinfunction "40_40") (pintype "unspecified"))
      (node (ref "U12") (pin "1") (pinfunction "GND_1") (pintype "unspecified"))
      (node (ref "U15") (pin "2") (pinfunction "VS-_2") (pintype "unspecified"))
      (node (ref "U16") (pin "2") (pinfunction "VS-_2") (pintype "unspecified"))
      (node (ref "U2") (pin "1") (pinfunction "GND_1") (pintype "unspecified"))
      (node (ref "U2") (pin "16") (pinfunction "FSSEL_16") (pintype "unspecified"))
      (node (ref "U2") (pin "18") (pinfunction "INT#/EXT_18") (pintype "unspecified"))
      (node (ref "U2") (pin "19") (pinfunction "OE#_19") (pintype "unspecified"))
      (node (ref "U2") (pin "20") (pinfunction "GND_20") (pintype "unspecified"))
      (node (ref "U2") (pin "26") (pinfunction "GND_26") (pintype "unspecified"))
    )
    (net (code "43") (name "Net-(C1-Pad2)") (class "Default")
      (node (ref "C1") (pin "2") (pinfunction "2_2") (pintype "unspecified"))
      (node (ref "C2") (pin "2") (pinfunction "2_2") (pintype "unspecified"))
      (node (ref "L1") (pin "2") (pinfunction "2_2") (pintype "unspecified"))
      (node (ref "L2") (pin "1") (pinfunction "1_1") (pintype "unspecified"))
    )
    (net (code "44") (name "Net-(C3-Pad1)") (class "Default")
      (node (ref "C3") (pin "1") (pinfunction "1_1") (pintype "unspecified"))
      (node (ref "L2") (pin "2") (pinfunction "2_2") (pintype "unspecified"))
    )
    (net (code "45") (name "Net-(C3-Pad2)") (class "Default")
      (node (ref "C3") (pin "2") (pinfunction "2_2") (pintype "unspecified"))
      (node (ref "C4") (pin "2") (pinfunction "2_2") (pintype "unspecified"))
      (node (ref "C5") (pin "1") (pinfunction "1_1") (pintype "unspecified"))
      (node (ref "L3") (pin "2") (pinfunction "2_2") (pintype "unspecified"))
    )
    (net (code "46") (name "Net-(C46-Pad2)") (class "Default")
      (node (ref "C46") (pin "2") (pinfunction "2_2") (pintype "unspecified"))
      (node (ref "L5") (pin "1") (pinfunction "1_1") (pintype "unspecified"))
    )
    (net (code "47") (name "Net-(C47-Pad1)") (class "Default")
      (node (ref "C47") (pin "1") (pinfunction "1_1") (pintype "unspecified"))
      (node (ref "L12") (pin "2") (pinfunction "2_2") (pintype "unspecified"))
    )
    (net (code "48") (name "Net-(C48-Pad2)") (class "Default")
      (node (ref "C48") (pin "2") (pinfunction "2_2") (pintype "unspecified"))
      (node (ref "L11") (pin "2") (pinfunction "2_2") (pintype "unspecified"))
      (node (ref "L12") (pin "1") (pinfunction "1_1") (pintype "unspecified"))
    )
    (net (code "49") (name "Net-(C49-Pad2)") (class "Default")
      (node (ref "C49") (pin "2") (pinfunction "2_2") (pintype "unspecified"))
      (node (ref "L10") (pin "2") (pinfunction "2_2") (pintype "unspecified"))
      (node (ref "L11") (pin "1") (pinfunction "1_1") (pintype "unspecified"))
    )
    (net (code "50") (name "Net-(C50-Pad2)") (class "Default")
      (node (ref "C50") (pin "2") (pinfunction "2_2") (pintype "unspecified"))
      (node (ref "L10") (pin "1") (pinfunction "1_1") (pintype "unspecified"))
      (node (ref "L5") (pin "2") (pinfunction "2_2") (pintype "unspecified"))
    )
    (net (code "51") (name "Net-(C51-Pad1)") (class "Default")
      (node (ref "C51") (pin "1") (pinfunction "1_1") (pintype "input"))
      (node (ref "R53") (pin "2") (pinfunction "2_2") (pintype "input"))
    )
    (net (code "52") (name "Net-(U1-+VA)") (class "Default")
      (node (ref "C44") (pin "1") (pinfunction "1_1") (pintype "unspecified"))
      (node (ref "L9") (pin "1") (pinfunction "1_1") (pintype "unspecified"))
      (node (ref "U1") (pin "24") (pinfunction "+VA_24") (pintype "unspecified"))
    )
    (net (code "53") (name "Net-(U1-BW)") (class "Default")
      (node (ref "C44") (pin "2") (pinfunction "2_2") (pintype "unspecified"))
      (node (ref "U1") (pin "19") (pinfunction "BW_19") (pintype "unspecified"))
    )
    (net (code "54") (name "Net-(U1-BYP)") (class "Default")
      (node (ref "C45") (pin "1") (pinfunction "1_1") (pintype "unspecified"))
      (node (ref "U1") (pin "23") (pinfunction "BYP_23") (pintype "unspecified"))
    )
    (net (code "55") (name "Net-(U1-Bit1)") (class "Default")
      (node (ref "R14") (pin "2") (pinfunction "2_2") (pintype "input"))
      (node (ref "U1") (pin "1") (pinfunction "Bit1_1") (pintype "unspecified"))
    )
    (net (code "56") (name "Net-(U1-Bit2)") (class "Default")
      (node (ref "R15") (pin "2") (pinfunction "2_2") (pintype "input"))
      (node (ref "U1") (pin "2") (pinfunction "Bit2_2") (pintype "unspecified"))
    )
    (net (code "57") (name "Net-(U1-Bit3)") (class "Default")
      (node (ref "R16") (pin "2") (pinfunction "2_2") (pintype "input"))
      (node (ref "U1") (pin "3") (pinfunction "Bit3_3") (pintype "unspecified"))
    )
    (net (code "58") (name "Net-(U1-Bit4)") (class "Default")
      (node (ref "R17") (pin "2") (pinfunction "2_2") (pintype "input"))
      (node (ref "U1") (pin "4") (pinfunction "Bit4_4") (pintype "unspecified"))
    )
    (net (code "59") (name "Net-(U1-Bit5)") (class "Default")
      (node (ref "R18") (pin "2") (pinfunction "2_2") (pintype "input"))
      (node (ref "U1") (pin "5") (pinfunction "Bit5_5") (pintype "unspecified"))
    )
    (net (code "60") (name "Net-(U1-Bit6)") (class "Default")
      (node (ref "R19") (pin "2") (pinfunction "2_2") (pintype "input"))
      (node (ref "U1") (pin "6") (pinfunction "Bit6_6") (pintype "unspecified"))
    )
    (net (code "61") (name "Net-(U1-Bit7)") (class "Default")
      (node (ref "R20") (pin "2") (pinfunction "2_2") (pintype "input"))
      (node (ref "U1") (pin "7") (pinfunction "Bit7_7") (pintype "unspecified"))
    )
    (net (code "62") (name "Net-(U1-Bit8)") (class "Default")
      (node (ref "R21") (pin "2") (pinfunction "2_2") (pintype "input"))
      (node (ref "U1") (pin "8") (pinfunction "Bit8_8") (pintype "unspecified"))
    )
    (net (code "63") (name "Net-(U1-Bit9)") (class "Default")
      (node (ref "R22") (pin "2") (pinfunction "2_2") (pintype "input"))
      (node (ref "U1") (pin "9") (pinfunction "Bit9_9") (pintype "unspecified"))
    )
    (net (code "64") (name "Net-(U1-Bit10)") (class "Default")
      (node (ref "R23") (pin "2") (pinfunction "2_2") (pintype "input"))
      (node (ref "U1") (pin "10") (pinfunction "Bit10_10") (pintype "unspecified"))
    )
    (net (code "65") (name "Net-(U1-Bit11)") (class "Default")
      (node (ref "R24") (pin "2") (pinfunction "2_2") (pintype "input"))
      (node (ref "U1") (pin "11") (pinfunction "Bit11_11") (pintype "unspecified"))
    )
    (net (code "66") (name "Net-(U1-Bit12)") (class "Default")
      (node (ref "R25") (pin "2") (pinfunction "2_2") (pintype "input"))
      (node (ref "U1") (pin "12") (pinfunction "Bit12_12") (pintype "unspecified"))
    )
    (net (code "67") (name "Net-(U1-CLK)") (class "Default")
      (node (ref "R39") (pin "1") (pinfunction "1_1") (pintype "input"))
      (node (ref "U1") (pin "28") (pinfunction "CLK_28") (pintype "unspecified"))
    )
    (net (code "68") (name "Net-(U1-FSA)") (class "Default")
      (node (ref "R41") (pin "2") (pinfunction "2_2") (pintype "unspecified"))
      (node (ref "U1") (pin "18") (pinfunction "FSA_18") (pintype "unspecified"))
    )
    (net (code "69") (name "Net-(U1-PD)") (class "Default")
      (node (ref "R38") (pin "2") (pinfunction "2_2") (pintype "input"))
      (node (ref "U1") (pin "15") (pinfunction "PD_15") (pintype "unspecified"))
    )
    (net (code "70") (name "Net-(U1-REFIN)") (class "Default")
      (node (ref "C43") (pin "2") (pinfunction "2_2") (pintype "unspecified"))
      (node (ref "U1") (pin "17") (pinfunction "REFIN_17") (pintype "unspecified"))
    )
    (net (code "71") (name "Net-(U2-Bit1(MSB))") (class "Default")
      (node (ref "R5") (pin "1") (pinfunction "1_1") (pintype "unspecified"))
      (node (ref "U2") (pin "2") (pinfunction "Bit1(MSB)_2") (pintype "unspecified"))
    )
    (net (code "72") (name "Net-(U2-Bit2)") (class "Default")
      (node (ref "R6") (pin "1") (pinfunction "1_1") (pintype "unspecified"))
      (node (ref "U2") (pin "3") (pinfunction "Bit2_3") (pintype "unspecified"))
    )
    (net (code "73") (name "Net-(U2-Bit3)") (class "Default")
      (node (ref "R7") (pin "1") (pinfunction "1_1") (pintype "unspecified"))
      (node (ref "U2") (pin "4") (pinfunction "Bit3_4") (pintype "unspecified"))
    )
    (net (code "74") (name "Net-(U2-Bit4)") (class "Default")
      (node (ref "R8") (pin "1") (pinfunction "1_1") (pintype "unspecified"))
      (node (ref "U2") (pin "5") (pinfunction "Bit4_5") (pintype "unspecified"))
    )
    (net (code "75") (name "Net-(U2-Bit5)") (class "Default")
      (node (ref "R9") (pin "1") (pinfunction "1_1") (pintype "unspecified"))
      (node (ref "U2") (pin "6") (pinfunction "Bit5_6") (pintype "unspecified"))
    )
    (net (code "76") (name "Net-(U2-Bit6)") (class "Default")
      (node (ref "R10") (pin "1") (pinfunction "1_1") (pintype "unspecified"))
      (node (ref "U2") (pin "7") (pinfunction "Bit6_7") (pintype "unspecified"))
    )
    (net (code "77") (name "Net-(U2-Bit7)") (class "Default")
      (node (ref "R11") (pin "1") (pinfunction "1_1") (pintype "unspecified"))
      (node (ref "U2") (pin "8") (pinfunction "Bit7_8") (pintype "unspecified"))
    )
    (net (code "78") (name "Net-(U2-Bit8)") (class "Default")
      (node (ref "R12") (pin "1") (pinfunction "1_1") (pintype "unspecified"))
      (node (ref "U2") (pin "9") (pinfunction "Bit8_9") (pintype "unspecified"))
    )
    (net (code "79") (name "Net-(U2-Bit9)") (class "Default")
      (node (ref "R13") (pin "1") (pinfunction "1_1") (pintype "unspecified"))
      (node (ref "U2") (pin "10") (pinfunction "Bit9_10") (pintype "unspecified"))
    )
    (net (code "80") (name "Net-(U2-Bit10)") (class "Default")
      (node (ref "R48") (pin "1") (pinfunction "1_1") (pintype "unspecified"))
      (node (ref "U2") (pin "11") (pinfunction "Bit10_11") (pintype "unspecified"))
    )
    (net (code "81") (name "Net-(U2-Bit11)") (class "Default")
      (node (ref "R49") (pin "1") (pinfunction "1_1") (pintype "unspecified"))
      (node (ref "U2") (pin "12") (pinfunction "Bit11_12") (pintype "unspecified"))
    )
    (net (code "82") (name "Net-(U2-Bit12(LSB))") (class "Default")
      (node (ref "R50") (pin "1") (pinfunction "1_1") (pintype "unspecified"))
      (node (ref "U2") (pin "13") (pinfunction "Bit12(LSB)_13") (pintype "unspecified"))
    )
    (net (code "83") (name "Net-(U2-CLK)") (class "Default")
      (node (ref "R40") (pin "1") (pinfunction "1_1") (pintype "input"))
      (node (ref "U2") (pin "14") (pinfunction "CLK_14") (pintype "unspecified"))
    )
    (net (code "84") (name "Net-(U2-REFB)") (class "Default")
      (node (ref "C15") (pin "1") (pinfunction "1_1") (pintype "unspecified"))
      (node (ref "C35") (pin "1") (pinfunction "1_1") (pintype "unspecified"))
      (node (ref "U2") (pin "21") (pinfunction "REFB_21") (pintype "unspecified"))
    )
    (net (code "85") (name "Net-(U2-REFT)") (class "Default")
      (node (ref "C13") (pin "1") (pinfunction "1_1") (pintype "unspecified"))
      (node (ref "C36") (pin "1") (pinfunction "1_1") (pintype "unspecified"))
      (node (ref "U2") (pin "22") (pinfunction "REFT_22") (pintype "unspecified"))
    )
    (net (code "86") (name "Net-(U15-+IN)") (class "Default")
      (node (ref "R51") (pin "2") (pinfunction "2_2") (pintype "input"))
      (node (ref "R52") (pin "1") (pinfunction "1_1") (pintype "input"))
      (node (ref "U15") (pin "3") (pinfunction "+IN_3") (pintype "unspecified"))
    )
    (net (code "87") (name "Net-(U15-OUT)") (class "Default")
      (node (ref "R52") (pin "2") (pinfunction "2_2") (pintype "input"))
      (node (ref "R53") (pin "1") (pinfunction "1_1") (pintype "input"))
      (node (ref "U15") (pin "1") (pinfunction "OUT_1") (pintype "output"))
    )
    (net (code "88") (name "Net-(U16-+IN)") (class "Default")
      (node (ref "R44") (pin "2") (pinfunction "2_2") (pintype "input"))
      (node (ref "R46") (pin "2") (pinfunction "2_2") (pintype "input"))
      (node (ref "U16") (pin "3") (pinfunction "+IN_3") (pintype "unspecified"))
    )
    (net (code "89") (name "Net-(U16--IN)") (class "Default")
      (node (ref "R43") (pin "2") (pinfunction "2_2") (pintype "input"))
      (node (ref "R45") (pin "1") (pinfunction "1_1") (pintype "input"))
      (node (ref "U16") (pin "4") (pinfunction "-IN_4") (pintype "unspecified"))
    )
    (net (code "90") (name "Net-(U16-OUT)") (class "Default")
      (node (ref "C46") (pin "1") (pinfunction "1_1") (pintype "unspecified"))
      (node (ref "R45") (pin "2") (pinfunction "2_2") (pintype "input"))
      (node (ref "U16") (pin "1") (pinfunction "OUT_1") (pintype "output"))
    )
    (net (code "91") (name "unconnected-(SCREW1-Pad1)") (class "Default")
      (node (ref "SCREW1") (pin "1") (pinfunction "1_1") (pintype "input"))
    )
    (net (code "92") (name "unconnected-(SCREW2-Pad1)") (class "Default")
      (node (ref "SCREW2") (pin "1") (pinfunction "1_1") (pintype "input"))
    )
    (net (code "93") (name "unconnected-(U1-NC-Pad13)") (class "Default")
      (node (ref "U1") (pin "13") (pinfunction "NC_13") (pintype "unspecified"))
    )
    (net (code "94") (name "unconnected-(U1-NC-Pad14)") (class "Default")
      (node (ref "U1") (pin "14") (pinfunction "NC_14") (pintype "unspecified"))
    )
    (net (code "95") (name "unconnected-(U1-NC-Pad25)") (class "Default")
      (node (ref "U1") (pin "25") (pinfunction "NC_25") (pintype "unspecified"))
    )
    (net (code "96") (name "unconnected-(U2-OTR-Pad17)") (class "Default")
      (node (ref "U2") (pin "17") (pinfunction "OTR_17") (pintype "unspecified"))
    )
    (net (code "97") (name "unconnected-(U10-Pad5)") (class "Default")
      (node (ref "U10") (pin "5") (pinfunction "5_5") (pintype "unspecified"))
    )
    (net (code "98") (name "unconnected-(U10-Pad17)") (class "Default")
      (node (ref "U10") (pin "17") (pinfunction "17_17") (pintype "unspecified"))
    )
    (net (code "99") (name "unconnected-(U10-Pad18)") (class "Default")
      (node (ref "U10") (pin "18") (pinfunction "18_18") (pintype "unspecified"))
    )
    (net (code "100") (name "unconnected-(U10-Pad19)") (class "Default")
      (node (ref "U10") (pin "19") (pinfunction "19_19") (pintype "unspecified"))
    )
    (net (code "101") (name "unconnected-(U10-Pad20)") (class "Default")
      (node (ref "U10") (pin "20") (pinfunction "20_20") (pintype "unspecified"))
    )
    (net (code "102") (name "unconnected-(U10-Pad21)") (class "Default")
      (node (ref "U10") (pin "21") (pinfunction "21_21") (pintype "unspecified"))
    )
    (net (code "103") (name "unconnected-(U10-Pad22)") (class "Default")
      (node (ref "U10") (pin "22") (pinfunction "22_22") (pintype "unspecified"))
    )
    (net (code "104") (name "unconnected-(U10-Pad23)") (class "Default")
      (node (ref "U10") (pin "23") (pinfunction "23_23") (pintype "unspecified"))
    )
    (net (code "105") (name "unconnected-(U10-Pad24)") (class "Default")
      (node (ref "U10") (pin "24") (pinfunction "24_24") (pintype "unspecified"))
    )
    (net (code "106") (name "unconnected-(U10-Pad25)") (class "Default")
      (node (ref "U10") (pin "25") (pinfunction "25_25") (pintype "unspecified"))
    )
    (net (code "107") (name "unconnected-(U10-Pad26)") (class "Default")
      (node (ref "U10") (pin "26") (pinfunction "26_26") (pintype "unspecified"))
    )
  )
)
